# OpenPLCv0_2_0_RS485.net
KiCad netlist of a schematic drawn in Altium Designer
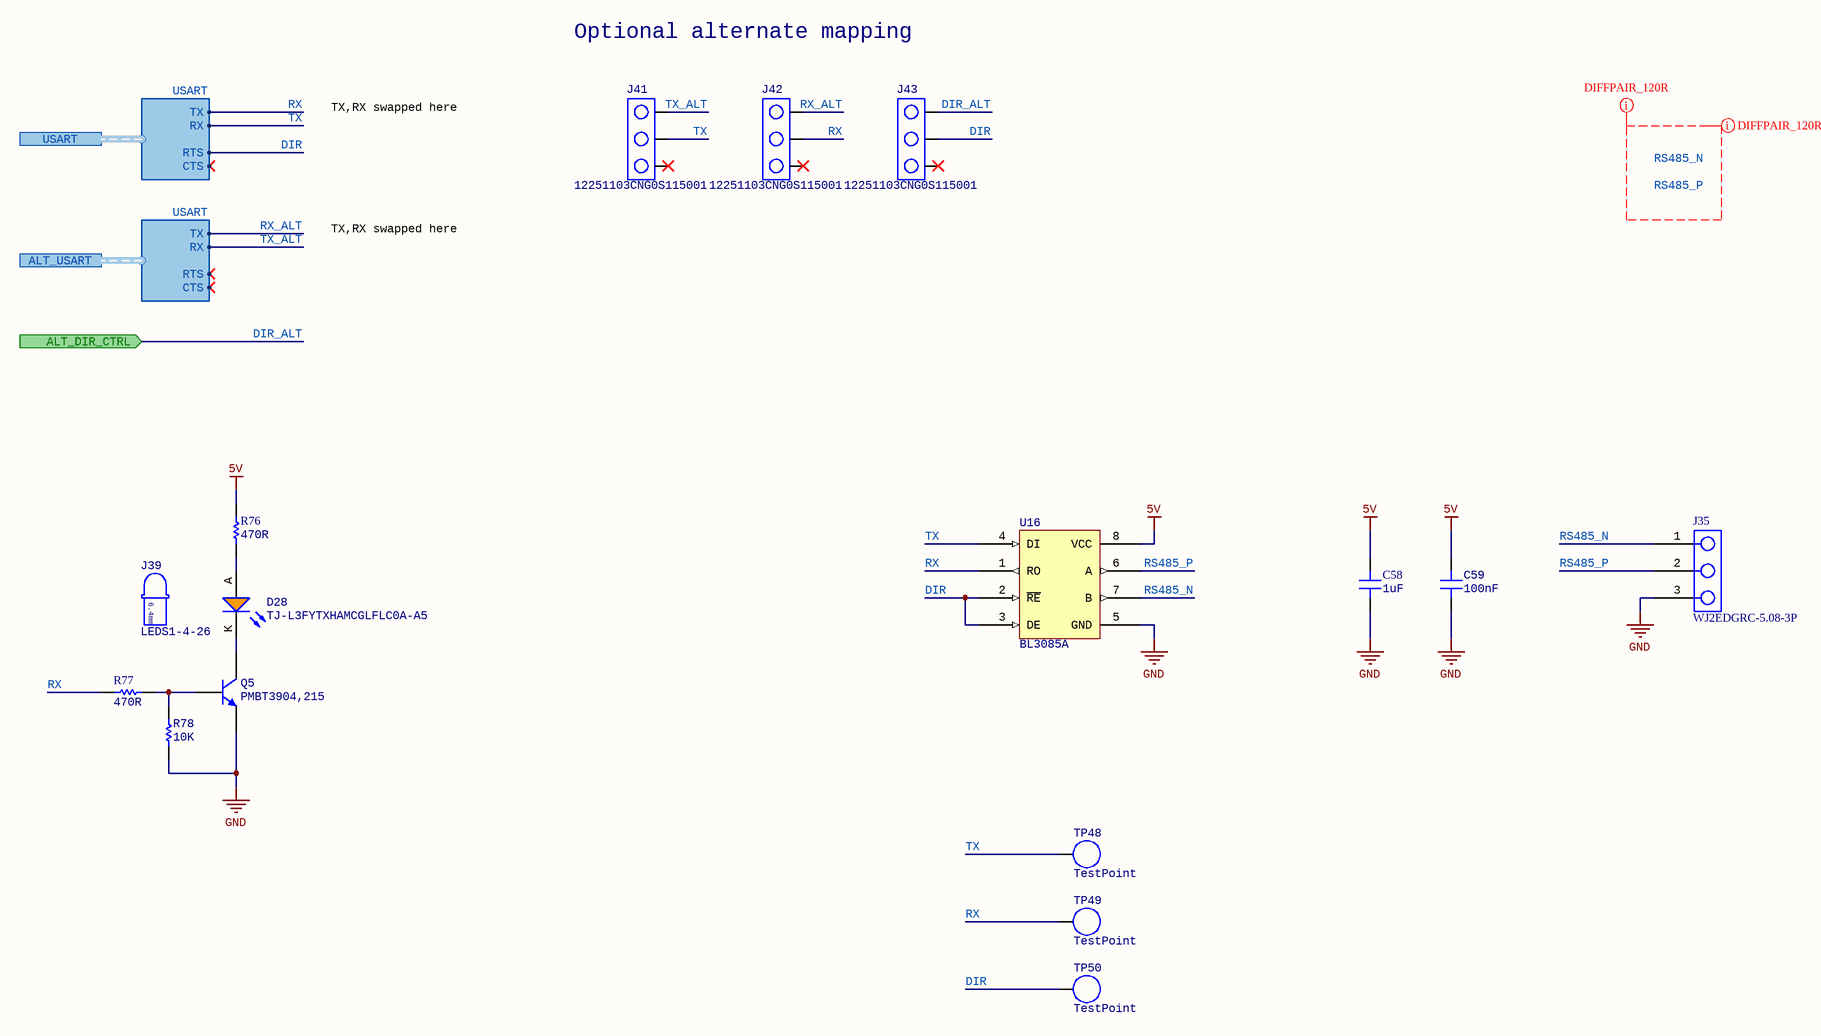
[diagram p0: OpenPLCv0.2.0_RS485.SchDoc]

(export (version "E")
  (design (tool "Eeschema 10.0.6"))
  (components
    (comp (ref "C58")
      (value "CC0603KRX5R9BB105")
      (footprint "SMD_CAP_0603(0201)_N")
      (description "1uF ±10% 50V X5R 0603 Multilayer Ceramic Capacitors MLCC - SMD/SMT RoHS")
      (fields (field (name "TOLERANCE") "10%") (field (name "CAPACITANCE") "1uF"))
      (libsource (lib "BrauV2_Capacitor") (part "1uF 0603 50V 10%"))
    )
    (comp (ref "C59")
      (value "CC0402KRX5R6BB104")
      (footprint "SMD_CAP_0402(1005)_N")
      (description "100nF ±10% 10V X5R 0402 Multilayer Ceramic Capacitors MLCC - SMD/SMT RoHS")
      (fields (field (name "TOLERANCE") "10%") (field (name "CAPACITANCE") "100nF"))
      (libsource (lib "BrauV2_Capacitor") (part "100nF 0402 10V 10%"))
    )
    (comp (ref "D28")
      (value "TJ-L3FYTXHAMCGLFLC0A-A5")
      (footprint "LED_3MM_SPACED_6.4MM_YELLOW")
      (description "600nm~610nm 1.8V~2.6V - - Through Hole Light Emitting Diodes (LED) ROHS 3mm")
      (libsource (lib "OpenPLCv0.2.0_Diode") (part "TJ-L3FYTXHAMCGLFLC0A-A5"))
    )
    (comp (ref "J35")
      (value "WJ2EDGRC-5.08-3P")
      (footprint "796638-3_BoardEdgeAlt")
      (description "Covered（4Sided） 3 1 0.200\"（5.08mm） 3 P=5.08mm Pluggable System Terminal Block RoHS")
      (libsource (lib "OpenPLCv0.2.0_Connector") (part "WJ2EDGRC-5.08-3P"))
    )
    (comp (ref "J39")
      (value "LEDS1-4-26")
      (footprint "3MM_LED_SPACER_6.4MM")
      (description "3mm LED spacer 6.4mm height")
      (libsource (lib "BrauV2_Misc") (part "LEDS1-4-26"))
    )
    (comp (ref "J41")
      (value "12251103CNG0S115001")
      (footprint "Header_3POS")
      (description "Pin Header 3 1 right-angle，180degrees 2.54mm Through Hole,P=2.54mm Pin Header & Female Header RoHS")
      (libsource (lib "BrauV2_Connector") (part "3-way Jumper"))
    )
    (comp (ref "J42")
      (value "12251103CNG0S115001")
      (footprint "Header_3POS")
      (description "Pin Header 3 1 right-angle，180degrees 2.54mm Through Hole,P=2.54mm Pin Header & Female Header RoHS")
      (libsource (lib "BrauV2_Connector") (part "3-way Jumper"))
    )
    (comp (ref "J43")
      (value "12251103CNG0S115001")
      (footprint "Header_3POS")
      (description "Pin Header 3 1 right-angle，180degrees 2.54mm Through Hole,P=2.54mm Pin Header & Female Header RoHS")
      (libsource (lib "BrauV2_Connector") (part "3-way Jumper"))
    )
    (comp (ref "Q5")
      (value "PMBT3904,215")
      (footprint "SOT23-3")
      (description "NPN 200mA 40V 250mW SOT-23(SOT-23-3) Transistors (NPN/PNP) RoHS")
      (libsource (lib "BrauV2_Transistor") (part "PMBT3904,215"))
    )
    (comp (ref "R76")
      (value "RC0402FR-07470RL")
      (footprint "SMD_RES_0402(1005)_N")
      (description "470Ω ±1% 1/16W ±100ppm/℃ 0402 Chip Resistor - Surface Mount RoHS")
      (fields (field (name "TOLERANCE") "1%") (field (name "RESISTANCE") "470R"))
      (libsource (lib "BrauV2_Resistor") (part "470R 0402 1% 1W"))
    )
    (comp (ref "R77")
      (value "RC0402FR-07470RL")
      (footprint "SMD_RES_0402(1005)_N")
      (description "470Ω ±1% 1/16W ±100ppm/℃ 0402 Chip Resistor - Surface Mount RoHS")
      (fields (field (name "TOLERANCE") "1%") (field (name "RESISTANCE") "470R"))
      (libsource (lib "BrauV2_Resistor") (part "470R 0402 1% 1W"))
    )
    (comp (ref "R78")
      (value "RC0402FR-0710KL")
      (footprint "SMD_RES_0402(1005)_N")
      (description "10kΩ ±1% 1/16W ±100ppm/℃ 0402 Chip Resistor - Surface Mount RoHS")
      (fields (field (name "TOLERANCE") "1%") (field (name "RESISTANCE") "10K"))
      (libsource (lib "BrauV2_Resistor") (part "10K 0402 1% 1/16W"))
    )
    (comp (ref "TP48")
      (value "TestPoint")
      (footprint "Pad")
      (libsource (lib "OpenPLCv0.2.0_Misc") (part "Test point"))
    )
    (comp (ref "TP49")
      (value "TestPoint")
      (footprint "Pad")
      (libsource (lib "OpenPLCv0.2.0_Misc") (part "Test point"))
    )
    (comp (ref "TP50")
      (value "TestPoint")
      (footprint "Pad")
      (libsource (lib "OpenPLCv0.2.0_Misc") (part "Test point"))
    )
    (comp (ref "U16")
      (value "BL3085A")
      (footprint "SOIC-8-3.9mm")
      (description "SOIC-8_150mil RS-485/RS-422 ICs ROHS (MAX485 clone)")
      (libsource (lib "BrauV2_IC") (part "BL3085A"))
    )
  )
  (nets
    (net (code "2") (name "/DIR") (class "Default")
      (node (ref "J43") (pin "2") (pinfunction "2_2") (pintype "passive"))
      (node (ref "TP50") (pin "1") (pinfunction "1_1") (pintype "passive"))
      (node (ref "U16") (pin "2") (pinfunction "~{RE}_2") (pintype "input"))
      (node (ref "U16") (pin "3") (pinfunction "DE_3") (pintype "input"))
    )
    (net (code "3") (name "/DIR_ALT") (class "Default")
      (node (ref "J43") (pin "1") (pinfunction "1_1") (pintype "passive"))
    )
    (net (code "4") (name "/RS485_N") (class "Default")
      (node (ref "J35") (pin "1") (pinfunction "1_1") (pintype "passive"))
      (node (ref "U16") (pin "7") (pinfunction "B_7") (pintype "output"))
    )
    (net (code "5") (name "/RS485_P") (class "Default")
      (node (ref "J35") (pin "2") (pinfunction "2_2") (pintype "passive"))
      (node (ref "U16") (pin "6") (pinfunction "A_6") (pintype "output"))
    )
    (net (code "6") (name "/RX") (class "Default")
      (node (ref "J42") (pin "2") (pinfunction "2_2") (pintype "passive"))
      (node (ref "R77") (pin "2") (pinfunction "2_2") (pintype "passive"))
      (node (ref "TP49") (pin "1") (pinfunction "1_1") (pintype "passive"))
      (node (ref "U16") (pin "1") (pinfunction "RO_1") (pintype "output"))
    )
    (net (code "7") (name "/RX_ALT") (class "Default")
      (node (ref "J42") (pin "1") (pinfunction "1_1") (pintype "passive"))
    )
    (net (code "8") (name "/TX") (class "Default")
      (node (ref "J41") (pin "2") (pinfunction "2_2") (pintype "passive"))
      (node (ref "TP48") (pin "1") (pinfunction "1_1") (pintype "passive"))
      (node (ref "U16") (pin "4") (pinfunction "DI_4") (pintype "input"))
    )
    (net (code "9") (name "/TX_ALT") (class "Default")
      (node (ref "J41") (pin "1") (pinfunction "1_1") (pintype "passive"))
    )
    (net (code "11") (name "5V") (class "Default")
      (node (ref "C58") (pin "2") (pinfunction "2_2") (pintype "passive"))
      (node (ref "C59") (pin "2") (pinfunction "2_2") (pintype "passive"))
      (node (ref "R76") (pin "2") (pinfunction "2_2") (pintype "passive"))
      (node (ref "U16") (pin "8") (pinfunction "VCC_8") (pintype "power_in"))
    )
    (net (code "12") (name "GND") (class "Default")
      (node (ref "C58") (pin "1") (pinfunction "1_1") (pintype "passive"))
      (node (ref "C59") (pin "1") (pinfunction "1_1") (pintype "passive"))
      (node (ref "J35") (pin "3") (pinfunction "3_3") (pintype "passive"))
      (node (ref "Q5") (pin "2") (pinfunction "E_2") (pintype "passive"))
      (node (ref "R78") (pin "1") (pinfunction "1_1") (pintype "passive"))
      (node (ref "U16") (pin "5") (pinfunction "GND_5") (pintype "power_in"))
    )
    (net (code "13") (name "Net-(D28-PadA)") (class "Default")
      (node (ref "D28") (pin "A") (pinfunction "A_A") (pintype "passive"))
      (node (ref "R76") (pin "1") (pinfunction "1_1") (pintype "passive"))
    )
    (net (code "14") (name "Net-(Q5-B)") (class "Default")
      (node (ref "Q5") (pin "1") (pinfunction "B_1") (pintype "passive"))
      (node (ref "R77") (pin "1") (pinfunction "1_1") (pintype "passive"))
      (node (ref "R78") (pin "2") (pinfunction "2_2") (pintype "passive"))
    )
    (net (code "15") (name "Net-(Q5-C)") (class "Default")
      (node (ref "D28") (pin "K") (pinfunction "K_K") (pintype "passive"))
      (node (ref "Q5") (pin "3") (pinfunction "C_3") (pintype "passive"))
    )
    (net (code "16") (name "unconnected-(J41-Pad3)") (class "Default")
      (node (ref "J41") (pin "3") (pinfunction "3_3") (pintype "passive+no_connect"))
    )
    (net (code "17") (name "unconnected-(J42-Pad3)") (class "Default")
      (node (ref "J42") (pin "3") (pinfunction "3_3") (pintype "passive+no_connect"))
    )
    (net (code "18") (name "unconnected-(J43-Pad3)") (class "Default")
      (node (ref "J43") (pin "3") (pinfunction "3_3") (pintype "passive+no_connect"))
    )
  )
)
